# k1fm_wspr_tx-1_1.net
KiCad netlist of a schematic drawn in EAGLE
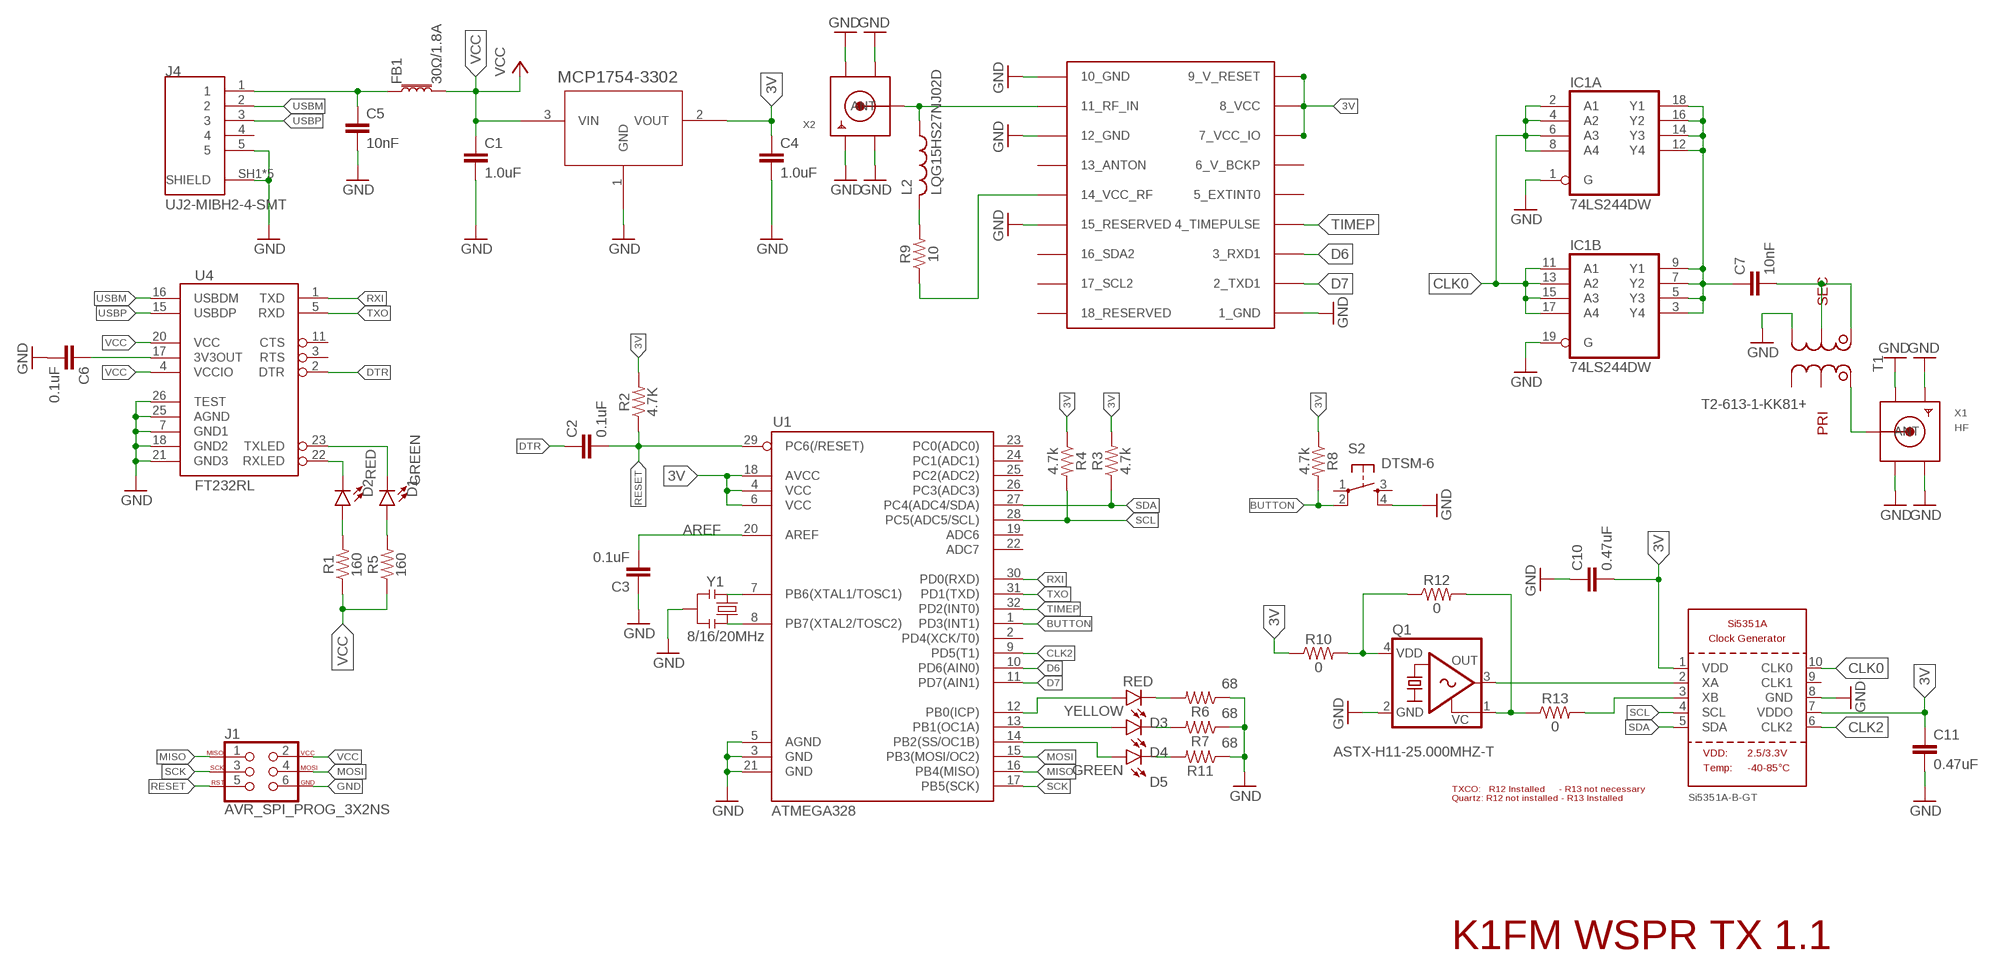
[diagram p0: schematic, sheet 1]

(export (version "E")
  (design (tool "Eeschema 10.0.6"))
  (components
    (comp (ref "C1")
      (value "1.0uF")
      (footprint "eagle-import:0603")
      (libsource (lib "eagle-import") (part "1.0UF-0603-16V-10%"))
    )
    (comp (ref "C2")
      (value "0.1uF")
      (footprint "eagle-import:0603")
      (libsource (lib "eagle-import") (part "0.1UF-0603-25V-5%"))
    )
    (comp (ref "C3")
      (value "0.1uF")
      (footprint "eagle-import:0603")
      (libsource (lib "eagle-import") (part "0.1UF-0603-25V-5%"))
    )
    (comp (ref "C4")
      (value "1.0uF")
      (footprint "eagle-import:0603")
      (libsource (lib "eagle-import") (part "1.0UF-0603-16V-10%"))
    )
    (comp (ref "C5")
      (value "10nF")
      (footprint "eagle-import:0603")
      (libsource (lib "eagle-import") (part "1.0UF-0603-16V-10%"))
    )
    (comp (ref "C6")
      (value "0.1uF")
      (footprint "eagle-import:0603")
      (libsource (lib "eagle-import") (part "0.1UF-0603-25V-5%"))
    )
    (comp (ref "C7")
      (value "10nF")
      (footprint "eagle-import:0603")
      (libsource (lib "eagle-import") (part "1.0UF-0603-16V-10%"))
    )
    (comp (ref "C10")
      (value "0.47uF")
      (footprint "eagle-import:0603")
      (libsource (lib "eagle-import") (part "0.1UF-0603-25V-5%"))
    )
    (comp (ref "C11")
      (value "0.47uF")
      (footprint "eagle-import:0603")
      (libsource (lib "eagle-import") (part "0.1UF-0603-25V-5%"))
    )
    (comp (ref "D1")
      (value "GREEN")
      (footprint "eagle-import:LED-0603")
      (libsource (lib "eagle-import") (part "LED0603"))
    )
    (comp (ref "D2")
      (value "RED")
      (footprint "eagle-import:LED-0603")
      (libsource (lib "eagle-import") (part "LED0603"))
    )
    (comp (ref "D3")
      (value "RED")
      (footprint "eagle-import:LED-0603")
      (libsource (lib "eagle-import") (part "LED0603"))
    )
    (comp (ref "D4")
      (value "YELLOW")
      (footprint "eagle-import:LED-0603")
      (libsource (lib "eagle-import") (part "LED0603"))
    )
    (comp (ref "D5")
      (value "GREEN")
      (footprint "eagle-import:LED-0603")
      (libsource (lib "eagle-import") (part "LED0603"))
    )
    (comp (ref "FB1")
      (value "30Ω/1.8A")
      (footprint "eagle-import:0603")
      (libsource (lib "eagle-import") (part "FERRITE_BEAD-0603"))
    )
    (comp (ref "GPS1")
      (value "UBLOX_MAX")
      (footprint "eagle-import:UBLOX_MAX")
      (libsource (lib "eagle-import") (part "UBLOX_MAX"))
    )
    (comp (ref "IC1")
      (value "74LS244DW")
      (footprint "eagle-import:SO20W")
      (libsource (lib "eagle-import") (part "74244DWLS"))
    )
    (comp (ref "J1")
      (value "AVR_SPI_PROG_3X2NS")
      (footprint "eagle-import:2X3-NS")
      (libsource (lib "eagle-import") (part "AVR_SPI_PROG_3X2NS"))
    )
    (comp (ref "J4")
      (value "UJ2-MIBH2-4-SMT")
      (footprint "eagle-import:CUI_UJ2-MIBH2-4-SMT")
      (fields (field (name "MANUFACTURER") "CUI INC"))
      (libsource (lib "eagle-import") (part "UJ2-MIBH2-4-SMT"))
    )
    (comp (ref "L2")
      (value "LQG15HS27NJ02D")
      (footprint "eagle-import:RESC0402_M")
      (libsource (lib "eagle-import") (part "INDUCTOR_0402_M"))
    )
    (comp (ref "Q1")
      (value "ASTX-H11-25.000MHZ-T")
      (footprint "eagle-import:3.2X2.5_KXO-84")
      (libsource (lib "eagle-import") (part "KXO-VCXO-SINE-84"))
    )
    (comp (ref "R1")
      (value "160")
      (footprint "eagle-import:0603")
      (libsource (lib "eagle-import") (part "4.7KOHM-0603-1/10W-1%"))
    )
    (comp (ref "R2")
      (value "4.7K")
      (footprint "eagle-import:0603")
      (libsource (lib "eagle-import") (part "10KOHM-0603-1/10W-1%"))
    )
    (comp (ref "R3")
      (value "4.7k")
      (footprint "eagle-import:0603")
      (libsource (lib "eagle-import") (part "4.7KOHM-0603-1/10W-1%"))
    )
    (comp (ref "R4")
      (value "4.7k")
      (footprint "eagle-import:0603")
      (libsource (lib "eagle-import") (part "4.7KOHM-0603-1/10W-1%"))
    )
    (comp (ref "R5")
      (value "160")
      (footprint "eagle-import:0603")
      (libsource (lib "eagle-import") (part "4.7KOHM-0603-1/10W-1%"))
    )
    (comp (ref "R6")
      (value "68")
      (footprint "eagle-import:0603")
      (libsource (lib "eagle-import") (part "4.7KOHM-0603-1/10W-1%"))
    )
    (comp (ref "R7")
      (value "68")
      (footprint "eagle-import:0603")
      (libsource (lib "eagle-import") (part "4.7KOHM-0603-1/10W-1%"))
    )
    (comp (ref "R8")
      (value "4.7k")
      (footprint "eagle-import:0603")
      (libsource (lib "eagle-import") (part "4.7KOHM-0603-1/10W-1%"))
    )
    (comp (ref "R9")
      (value "10")
      (footprint "eagle-import:0603")
      (libsource (lib "eagle-import") (part "10KOHM-0603-1/10W-1%"))
    )
    (comp (ref "R10")
      (value "0")
      (footprint "eagle-import:0603")
      (libsource (lib "eagle-import") (part "4.7KOHM-0603-1/10W-1%"))
    )
    (comp (ref "R11")
      (value "68")
      (footprint "eagle-import:0603")
      (libsource (lib "eagle-import") (part "4.7KOHM-0603-1/10W-1%"))
    )
    (comp (ref "R12")
      (value "0")
      (footprint "eagle-import:0603")
      (libsource (lib "eagle-import") (part "4.7KOHM-0603-1/10W-1%"))
    )
    (comp (ref "R13")
      (value "0")
      (footprint "eagle-import:0603")
      (libsource (lib "eagle-import") (part "4.7KOHM-0603-1/10W-1%"))
    )
    (comp (ref "S2")
      (value "DTSM-6")
      (footprint "eagle-import:DTSM-6")
      (libsource (lib "eagle-import") (part "DTSM-6"))
    )
    (comp (ref "T1")
      (value "T2-613-1-KK81+")
      (footprint "eagle-import:KK81")
      (libsource (lib "eagle-import") (part "TT1-6"))
    )
    (comp (ref "U1")
      (value "ATMEGA328")
      (footprint "eagle-import:TQFP32-08")
      (libsource (lib "eagle-import") (part "ATMEGA168"))
    )
    (comp (ref "U2")
      (value "Si5351A-B-GT")
      (footprint "eagle-import:MSOP10")
      (libsource (lib "eagle-import") (part "SI5351A"))
    )
    (comp (ref "U3")
      (value "MCP1754X-XXXXX/C")
      (footprint "eagle-import:SOT-23A_MC")
      (libsource (lib "eagle-import") (part "MCP1754X-XXXXX/C"))
    )
    (comp (ref "U4")
      (value "FT232RL")
      (footprint "eagle-import:SSOP28DB")
      (libsource (lib "eagle-import") (part "FT232RL-BASICSSOP"))
    )
    (comp (ref "X1")
      (value "HF")
      (footprint "eagle-import:SMA_EDGELAUNCH")
      (libsource (lib "eagle-import") (part "SMACONNECTOR_EDGE"))
    )
    (comp (ref "X2")
      (value "SMACONNECTOR_EDGE")
      (footprint "eagle-import:SMA_EDGELAUNCH")
      (libsource (lib "eagle-import") (part "SMACONNECTOR_EDGE"))
    )
    (comp (ref "Y1")
      (value "8/16/20MHz")
      (footprint "eagle-import:RESONATOR-SMD-1_1")
      (libsource (lib "eagle-import") (part "RESONATOR1{colon}1"))
    )
  )
  (nets
    (net (code "1") (name "/AREF") (class "Default")
      (node (ref "C3") (pin "2") (pinfunction "2_2") (pintype "passive"))
      (node (ref "U1") (pin "20") (pinfunction "AREF_20") (pintype "bidirectional"))
    )
    (net (code "2") (name "3V") (class "Default")
      (node (ref "C10") (pin "2") (pinfunction "2_2") (pintype "passive"))
      (node (ref "C11") (pin "1") (pinfunction "1_1") (pintype "passive"))
      (node (ref "C4") (pin "1") (pinfunction "1_1") (pintype "passive"))
      (node (ref "GPS1") (pin "7_VCC_IO") (pinfunction "7_VCC_IO_7_VCC_IO") (pintype "power_in"))
      (node (ref "GPS1") (pin "8_VCC") (pinfunction "8_VCC_8_VCC") (pintype "power_in"))
      (node (ref "GPS1") (pin "9_V_RESET") (pinfunction "9_V_RESET_9_V_RESET") (pintype "power_in"))
      (node (ref "R10") (pin "1") (pinfunction "1_1") (pintype "passive"))
      (node (ref "R2") (pin "2") (pinfunction "2_2") (pintype "passive"))
      (node (ref "R3") (pin "2") (pinfunction "2_2") (pintype "passive"))
      (node (ref "R4") (pin "1") (pinfunction "1_1") (pintype "passive"))
      (node (ref "R8") (pin "1") (pinfunction "1_1") (pintype "passive"))
      (node (ref "U1") (pin "18") (pinfunction "AVCC_18") (pintype "bidirectional"))
      (node (ref "U1") (pin "4") (pinfunction "VCC_4") (pintype "bidirectional"))
      (node (ref "U1") (pin "6") (pinfunction "VCC_6") (pintype "bidirectional"))
      (node (ref "U2") (pin "1") (pinfunction "VDD_1") (pintype "power_in"))
      (node (ref "U2") (pin "7") (pinfunction "VDDO_7") (pintype "power_in"))
      (node (ref "U3") (pin "2") (pinfunction "VOUT_2") (pintype "passive"))
    )
    (net (code "3") (name "BUTTON") (class "Default")
      (node (ref "R8") (pin "2") (pinfunction "2_2") (pintype "passive"))
      (node (ref "S2") (pin "2") (pinfunction "2_2") (pintype "passive"))
      (node (ref "U1") (pin "1") (pinfunction "PD3(INT1)_1") (pintype "bidirectional"))
    )
    (net (code "4") (name "CLK0") (class "Default")
      (node (ref "IC1") (pin "11") (pinfunction "A1_11") (pintype "input"))
      (node (ref "IC1") (pin "13") (pinfunction "A2_13") (pintype "input"))
      (node (ref "IC1") (pin "15") (pinfunction "A3_15") (pintype "input"))
      (node (ref "IC1") (pin "17") (pinfunction "A4_17") (pintype "input"))
      (node (ref "IC1") (pin "2") (pinfunction "A1_2") (pintype "input"))
      (node (ref "IC1") (pin "4") (pinfunction "A2_4") (pintype "input"))
      (node (ref "IC1") (pin "6") (pinfunction "A3_6") (pintype "input"))
      (node (ref "IC1") (pin "8") (pinfunction "A4_8") (pintype "input"))
      (node (ref "U2") (pin "10") (pinfunction "CLK0_10") (pintype "output"))
    )
    (net (code "5") (name "CLK2") (class "Default")
      (node (ref "U1") (pin "9") (pinfunction "PD5(T1)_9") (pintype "bidirectional"))
      (node (ref "U2") (pin "6") (pinfunction "CLK2_6") (pintype "output"))
    )
    (net (code "6") (name "D6") (class "Default")
      (node (ref "GPS1") (pin "3_RXD1") (pinfunction "3_RXD1_3_RXD1") (pintype "bidirectional"))
      (node (ref "U1") (pin "10") (pinfunction "PD6(AIN0)_10") (pintype "bidirectional"))
    )
    (net (code "7") (name "D7") (class "Default")
      (node (ref "GPS1") (pin "2_TXD1") (pinfunction "2_TXD1_2_TXD1") (pintype "bidirectional"))
      (node (ref "U1") (pin "11") (pinfunction "PD7(AIN1)_11") (pintype "bidirectional"))
    )
    (net (code "8") (name "DTR") (class "Default")
      (node (ref "C2") (pin "1") (pinfunction "1_1") (pintype "passive"))
      (node (ref "U4") (pin "2") (pinfunction "DTR_2") (pintype "bidirectional"))
    )
    (net (code "9") (name "GND") (class "Default")
      (node (ref "C1") (pin "2") (pinfunction "2_2") (pintype "passive"))
      (node (ref "C10") (pin "1") (pinfunction "1_1") (pintype "passive"))
      (node (ref "C11") (pin "2") (pinfunction "2_2") (pintype "passive"))
      (node (ref "C3") (pin "1") (pinfunction "1_1") (pintype "passive"))
      (node (ref "C4") (pin "2") (pinfunction "2_2") (pintype "passive"))
      (node (ref "C5") (pin "2") (pinfunction "2_2") (pintype "passive"))
      (node (ref "C6") (pin "2") (pinfunction "2_2") (pintype "passive"))
      (node (ref "GPS1") (pin "10_GND") (pinfunction "10_GND_10_GND") (pintype "power_in"))
      (node (ref "GPS1") (pin "12_GND") (pinfunction "12_GND_12_GND") (pintype "power_in"))
      (node (ref "GPS1") (pin "15_RESERVED") (pinfunction "15_RESERVED_15_RESERVED") (pintype "bidirectional"))
      (node (ref "GPS1") (pin "1_GND") (pinfunction "1_GND_1_GND") (pintype "power_in"))
      (node (ref "IC1") (pin "1") (pinfunction "G_1") (pintype "input"))
      (node (ref "IC1") (pin "19") (pinfunction "G_19") (pintype "input"))
      (node (ref "J1") (pin "6") (pinfunction "6_6") (pintype "passive"))
      (node (ref "J4") (pin "5") (pinfunction "5_5") (pintype "passive"))
      (node (ref "J4") (pin "SH1") (pinfunction "SHIELD_SH1") (pintype "passive"))
      (node (ref "J4") (pin "SH2") (pinfunction "SHIELD_SH2") (pintype "passive"))
      (node (ref "J4") (pin "SH3") (pinfunction "SHIELD_SH3") (pintype "passive"))
      (node (ref "J4") (pin "SH4") (pinfunction "SHIELD_SH4") (pintype "passive"))
      (node (ref "J4") (pin "SH5") (pinfunction "SHIELD_SH5") (pintype "passive"))
      (node (ref "Q1") (pin "2") (pinfunction "GND_2") (pintype "power_in"))
      (node (ref "R11") (pin "1") (pinfunction "1_1") (pintype "passive"))
      (node (ref "R6") (pin "1") (pinfunction "1_1") (pintype "passive"))
      (node (ref "R7") (pin "1") (pinfunction "1_1") (pintype "passive"))
      (node (ref "S2") (pin "4") (pinfunction "4_4") (pintype "passive"))
      (node (ref "T1") (pin "1") (pinfunction "S2_1") (pintype "passive"))
      (node (ref "U1") (pin "21") (pinfunction "GND_21") (pintype "bidirectional"))
      (node (ref "U1") (pin "3") (pinfunction "GND_3") (pintype "bidirectional"))
      (node (ref "U1") (pin "5") (pinfunction "AGND_5") (pintype "bidirectional"))
      (node (ref "U2") (pin "8") (pinfunction "GND_8") (pintype "power_in"))
      (node (ref "U3") (pin "1") (pinfunction "GND_1") (pintype "passive"))
      (node (ref "U4") (pin "18") (pinfunction "GND2_18") (pintype "power_in"))
      (node (ref "U4") (pin "21") (pinfunction "GND3_21") (pintype "power_in"))
      (node (ref "U4") (pin "25") (pinfunction "AGND_25") (pintype "power_in"))
      (node (ref "U4") (pin "26") (pinfunction "TEST_26") (pintype "input"))
      (node (ref "U4") (pin "7") (pinfunction "GND1_7") (pintype "power_in"))
      (node (ref "X1") (pin "GND@1") (pinfunction "GND4_GND@1") (pintype "power_in"))
      (node (ref "X1") (pin "GND@2") (pinfunction "GND3_GND@2") (pintype "power_in"))
      (node (ref "X1") (pin "GND@3") (pinfunction "GND2_GND@3") (pintype "power_in"))
      (node (ref "X1") (pin "GND@4") (pinfunction "GND1_GND@4") (pintype "power_in"))
      (node (ref "X2") (pin "GND@1") (pinfunction "GND4_GND@1") (pintype "power_in"))
      (node (ref "X2") (pin "GND@2") (pinfunction "GND3_GND@2") (pintype "power_in"))
      (node (ref "X2") (pin "GND@3") (pinfunction "GND2_GND@3") (pintype "power_in"))
      (node (ref "X2") (pin "GND@4") (pinfunction "GND1_GND@4") (pintype "power_in"))
      (node (ref "Y1") (pin "2") (pinfunction "2_2") (pintype "passive"))
    )
    (net (code "10") (name "MISO") (class "Default")
      (node (ref "J1") (pin "1") (pinfunction "1_1") (pintype "passive"))
      (node (ref "U1") (pin "16") (pinfunction "PB4(MISO)_16") (pintype "bidirectional"))
    )
    (net (code "11") (name "MOSI") (class "Default")
      (node (ref "J1") (pin "4") (pinfunction "4_4") (pintype "passive"))
      (node (ref "U1") (pin "15") (pinfunction "PB3(MOSI/OC2)_15") (pintype "bidirectional"))
    )
    (net (code "12") (name "Net-(C5-Pad1)") (class "Default")
      (node (ref "C5") (pin "1") (pinfunction "1_1") (pintype "passive"))
      (node (ref "FB1") (pin "1") (pinfunction "1_1") (pintype "passive"))
      (node (ref "J4") (pin "1") (pinfunction "1_1") (pintype "passive"))
    )
    (net (code "13") (name "Net-(D1-PadA)") (class "Default")
      (node (ref "D1") (pin "A") (pinfunction "A_A") (pintype "passive"))
      (node (ref "R5") (pin "2") (pinfunction "2_2") (pintype "passive"))
    )
    (net (code "14") (name "Net-(D2-PadA)") (class "Default")
      (node (ref "D2") (pin "A") (pinfunction "A_A") (pintype "passive"))
      (node (ref "R1") (pin "2") (pinfunction "2_2") (pintype "passive"))
    )
    (net (code "15") (name "Net-(D3-PadC)") (class "Default")
      (node (ref "D3") (pin "C") (pinfunction "C_C") (pintype "passive"))
      (node (ref "R6") (pin "2") (pinfunction "2_2") (pintype "passive"))
    )
    (net (code "16") (name "Net-(D4-PadC)") (class "Default")
      (node (ref "D4") (pin "C") (pinfunction "C_C") (pintype "passive"))
      (node (ref "R7") (pin "2") (pinfunction "2_2") (pintype "passive"))
    )
    (net (code "17") (name "Net-(D5-PadC)") (class "Default")
      (node (ref "D5") (pin "C") (pinfunction "C_C") (pintype "passive"))
      (node (ref "R11") (pin "2") (pinfunction "2_2") (pintype "passive"))
    )
    (net (code "18") (name "Net-(GPS1-Pad14_VCC_RF)") (class "Default")
      (node (ref "GPS1") (pin "14_VCC_RF") (pinfunction "14_VCC_RF_14_VCC_RF") (pintype "bidirectional"))
      (node (ref "R9") (pin "1") (pinfunction "1_1") (pintype "passive"))
    )
    (net (code "19") (name "Net-(IC1A-Y1)") (class "Default")
      (node (ref "C7") (pin "1") (pinfunction "1_1") (pintype "passive"))
      (node (ref "IC1") (pin "12") (pinfunction "Y4_12") (pintype "tri_state"))
      (node (ref "IC1") (pin "14") (pinfunction "Y3_14") (pintype "tri_state"))
      (node (ref "IC1") (pin "16") (pinfunction "Y2_16") (pintype "tri_state"))
      (node (ref "IC1") (pin "18") (pinfunction "Y1_18") (pintype "tri_state"))
      (node (ref "IC1") (pin "3") (pinfunction "Y4_3") (pintype "tri_state"))
      (node (ref "IC1") (pin "5") (pinfunction "Y3_5") (pintype "tri_state"))
      (node (ref "IC1") (pin "7") (pinfunction "Y2_7") (pintype "tri_state"))
      (node (ref "IC1") (pin "9") (pinfunction "Y1_9") (pintype "tri_state"))
    )
    (net (code "20") (name "Net-(L2-Pad2)") (class "Default")
      (node (ref "L2") (pin "2") (pinfunction "2_2") (pintype "passive"))
      (node (ref "R9") (pin "2") (pinfunction "2_2") (pintype "passive"))
    )
    (net (code "21") (name "Net-(Q1-OUT)") (class "Default")
      (node (ref "Q1") (pin "3") (pinfunction "OUT_3") (pintype "output"))
      (node (ref "U2") (pin "2") (pinfunction "XA_2") (pintype "input"))
    )
    (net (code "22") (name "Net-(Q1-VC)") (class "Default")
      (node (ref "Q1") (pin "1") (pinfunction "VC_1") (pintype "input"))
      (node (ref "R12") (pin "2") (pinfunction "2_2") (pintype "passive"))
      (node (ref "R13") (pin "1") (pinfunction "1_1") (pintype "passive"))
    )
    (net (code "23") (name "Net-(Q1-VDD)") (class "Default")
      (node (ref "Q1") (pin "4") (pinfunction "VDD_4") (pintype "power_in"))
      (node (ref "R10") (pin "2") (pinfunction "2_2") (pintype "passive"))
      (node (ref "R12") (pin "1") (pinfunction "1_1") (pintype "passive"))
    )
    (net (code "24") (name "Net-(T1-P1)") (class "Default")
      (node (ref "T1") (pin "4") (pinfunction "P1_4") (pintype "passive"))
      (node (ref "X1") (pin "P") (pinfunction "ANT_P") (pintype "bidirectional"))
    )
    (net (code "25") (name "Net-(T1-S1)") (class "Default")
      (node (ref "C7") (pin "2") (pinfunction "2_2") (pintype "passive"))
      (node (ref "T1") (pin "2") (pinfunction "ST_2") (pintype "passive"))
      (node (ref "T1") (pin "3") (pinfunction "S1_3") (pintype "passive"))
    )
    (net (code "26") (name "Net-(U1-PB0(ICP))") (class "Default")
      (node (ref "D3") (pin "A") (pinfunction "A_A") (pintype "passive"))
      (node (ref "U1") (pin "12") (pinfunction "PB0(ICP)_12") (pintype "bidirectional"))
    )
    (net (code "27") (name "Net-(U1-PB1(OC1A))") (class "Default")
      (node (ref "D4") (pin "A") (pinfunction "A_A") (pintype "passive"))
      (node (ref "U1") (pin "13") (pinfunction "PB1(OC1A)_13") (pintype "bidirectional"))
    )
    (net (code "28") (name "Net-(U1-PB2(SS{slash}OC1B))") (class "Default")
      (node (ref "D5") (pin "A") (pinfunction "A_A") (pintype "passive"))
      (node (ref "U1") (pin "14") (pinfunction "PB2(SS/OC1B)_14") (pintype "bidirectional"))
    )
    (net (code "29") (name "Net-(U1-PB6(XTAL1{slash}TOSC1))") (class "Default")
      (node (ref "U1") (pin "7") (pinfunction "PB6(XTAL1/TOSC1)_7") (pintype "bidirectional"))
      (node (ref "Y1") (pin "1") (pinfunction "1_1") (pintype "passive"))
    )
    (net (code "30") (name "Net-(U1-PB7(XTAL2{slash}TOSC2))") (class "Default")
      (node (ref "U1") (pin "8") (pinfunction "PB7(XTAL2/TOSC2)_8") (pintype "bidirectional"))
      (node (ref "Y1") (pin "3") (pinfunction "3_3") (pintype "passive"))
    )
    (net (code "31") (name "Net-(U2-XB)") (class "Default")
      (node (ref "R13") (pin "2") (pinfunction "2_2") (pintype "passive"))
      (node (ref "U2") (pin "3") (pinfunction "XB_3") (pintype "input"))
    )
    (net (code "32") (name "Net-(U4-3V3OUT)") (class "Default")
      (node (ref "C6") (pin "1") (pinfunction "1_1") (pintype "passive"))
      (node (ref "U4") (pin "17") (pinfunction "3V3OUT_17") (pintype "output"))
    )
    (net (code "33") (name "Net-(U4-RXLED)") (class "Default")
      (node (ref "D2") (pin "C") (pinfunction "C_C") (pintype "passive"))
      (node (ref "U4") (pin "22") (pinfunction "RXLED_22") (pintype "bidirectional"))
    )
    (net (code "34") (name "Net-(U4-TXLED)") (class "Default")
      (node (ref "D1") (pin "C") (pinfunction "C_C") (pintype "passive"))
      (node (ref "U4") (pin "23") (pinfunction "TXLED_23") (pintype "bidirectional"))
    )
    (net (code "35") (name "Net-(X2-ANT)") (class "Default")
      (node (ref "GPS1") (pin "11_RF_IN") (pinfunction "11_RF_IN_11_RF_IN") (pintype "bidirectional"))
      (node (ref "L2") (pin "1") (pinfunction "1_1") (pintype "passive"))
      (node (ref "X2") (pin "P") (pinfunction "ANT_P") (pintype "bidirectional"))
    )
    (net (code "36") (name "RESET") (class "Default")
      (node (ref "C2") (pin "2") (pinfunction "2_2") (pintype "passive"))
      (node (ref "J1") (pin "5") (pinfunction "5_5") (pintype "passive"))
      (node (ref "R2") (pin "1") (pinfunction "1_1") (pintype "passive"))
      (node (ref "U1") (pin "29") (pinfunction "PC6(/RESET)_29") (pintype "bidirectional"))
    )
    (net (code "37") (name "RXI") (class "Default")
      (node (ref "U1") (pin "30") (pinfunction "PD0(RXD)_30") (pintype "bidirectional"))
      (node (ref "U4") (pin "1") (pinfunction "TXD_1") (pintype "output"))
    )
    (net (code "38") (name "SCK") (class "Default")
      (node (ref "J1") (pin "3") (pinfunction "3_3") (pintype "passive"))
      (node (ref "U1") (pin "17") (pinfunction "PB5(SCK)_17") (pintype "bidirectional"))
    )
    (net (code "39") (name "SCL") (class "Default")
      (node (ref "R4") (pin "2") (pinfunction "2_2") (pintype "passive"))
      (node (ref "U1") (pin "28") (pinfunction "PC5(ADC5/SCL)_28") (pintype "bidirectional"))
      (node (ref "U2") (pin "4") (pinfunction "SCL_4") (pintype "input"))
    )
    (net (code "40") (name "SDA") (class "Default")
      (node (ref "R3") (pin "1") (pinfunction "1_1") (pintype "passive"))
      (node (ref "U1") (pin "27") (pinfunction "PC4(ADC4/SDA)_27") (pintype "bidirectional"))
      (node (ref "U2") (pin "5") (pinfunction "SDA_5") (pintype "bidirectional"))
    )
    (net (code "41") (name "TIMEP") (class "Default")
      (node (ref "GPS1") (pin "4_TIMEPULSE") (pinfunction "4_TIMEPULSE_4_TIMEPULSE") (pintype "bidirectional"))
      (node (ref "U1") (pin "32") (pinfunction "PD2(INT0)_32") (pintype "bidirectional"))
    )
    (net (code "42") (name "TXO") (class "Default")
      (node (ref "U1") (pin "31") (pinfunction "PD1(TXD)_31") (pintype "bidirectional"))
      (node (ref "U4") (pin "5") (pinfunction "RXD_5") (pintype "input"))
    )
    (net (code "43") (name "USBM") (class "Default")
      (node (ref "J4") (pin "2") (pinfunction "2_2") (pintype "passive"))
      (node (ref "U4") (pin "16") (pinfunction "USBDM_16") (pintype "bidirectional"))
    )
    (net (code "44") (name "USBP") (class "Default")
      (node (ref "J4") (pin "3") (pinfunction "3_3") (pintype "passive"))
      (node (ref "U4") (pin "15") (pinfunction "USBDP_15") (pintype "bidirectional"))
    )
    (net (code "45") (name "VCC") (class "Default")
      (node (ref "C1") (pin "1") (pinfunction "1_1") (pintype "passive"))
      (node (ref "FB1") (pin "2") (pinfunction "2_2") (pintype "passive"))
      (node (ref "J1") (pin "2") (pinfunction "2_2") (pintype "passive"))
      (node (ref "R1") (pin "1") (pinfunction "1_1") (pintype "passive"))
      (node (ref "R5") (pin "1") (pinfunction "1_1") (pintype "passive"))
      (node (ref "U3") (pin "3") (pinfunction "VIN_3") (pintype "passive"))
      (node (ref "U4") (pin "20") (pinfunction "VCC_20") (pintype "power_in"))
      (node (ref "U4") (pin "4") (pinfunction "VCCIO_4") (pintype "power_in"))
    )
    (net (code "46") (name "unconnected-(GPS1-Pad5_EXTINT0)") (class "Default")
      (node (ref "GPS1") (pin "5_EXTINT0") (pinfunction "5_EXTINT0_5_EXTINT0") (pintype "bidirectional"))
    )
    (net (code "47") (name "unconnected-(GPS1-Pad6_V_BCKP)") (class "Default")
      (node (ref "GPS1") (pin "6_V_BCKP") (pinfunction "6_V_BCKP_6_V_BCKP") (pintype "bidirectional"))
    )
    (net (code "48") (name "unconnected-(GPS1-Pad13_ANTON)") (class "Default")
      (node (ref "GPS1") (pin "13_ANTON") (pinfunction "13_ANTON_13_ANTON") (pintype "bidirectional"))
    )
    (net (code "49") (name "unconnected-(GPS1-Pad16_SDA2)") (class "Default")
      (node (ref "GPS1") (pin "16_SDA2") (pinfunction "16_SDA2_16_SDA2") (pintype "bidirectional"))
    )
    (net (code "50") (name "unconnected-(GPS1-Pad17_SCL2)") (class "Default")
      (node (ref "GPS1") (pin "17_SCL2") (pinfunction "17_SCL2_17_SCL2") (pintype "bidirectional"))
    )
    (net (code "51") (name "unconnected-(GPS1-Pad18_RESERVED)") (class "Default")
      (node (ref "GPS1") (pin "18_RESERVED") (pinfunction "18_RESERVED_18_RESERVED") (pintype "bidirectional"))
    )
    (net (code "52") (name "unconnected-(J4-Pad4)") (class "Default")
      (node (ref "J4") (pin "4") (pinfunction "4_4") (pintype "passive"))
    )
    (net (code "53") (name "unconnected-(S2-Pad1)") (class "Default")
      (node (ref "S2") (pin "1") (pinfunction "1_1") (pintype "passive"))
    )
    (net (code "54") (name "unconnected-(S2-Pad3)") (class "Default")
      (node (ref "S2") (pin "3") (pinfunction "3_3") (pintype "passive"))
    )
    (net (code "55") (name "unconnected-(T1-P2-Pad6)") (class "Default")
      (node (ref "T1") (pin "6") (pinfunction "P2_6") (pintype "passive"))
    )
    (net (code "56") (name "unconnected-(T1-PT-Pad5)") (class "Default")
      (node (ref "T1") (pin "5") (pinfunction "PT_5") (pintype "passive"))
    )
    (net (code "57") (name "unconnected-(U1-ADC6-Pad19)") (class "Default")
      (node (ref "U1") (pin "19") (pinfunction "ADC6_19") (pintype "bidirectional"))
    )
    (net (code "58") (name "unconnected-(U1-ADC7-Pad22)") (class "Default")
      (node (ref "U1") (pin "22") (pinfunction "ADC7_22") (pintype "bidirectional"))
    )
    (net (code "59") (name "unconnected-(U1-PC0(ADC0)-Pad23)") (class "Default")
      (node (ref "U1") (pin "23") (pinfunction "PC0(ADC0)_23") (pintype "bidirectional"))
    )
    (net (code "60") (name "unconnected-(U1-PC1(ADC1)-Pad24)") (class "Default")
      (node (ref "U1") (pin "24") (pinfunction "PC1(ADC1)_24") (pintype "bidirectional"))
    )
    (net (code "61") (name "unconnected-(U1-PC2(ADC2)-Pad25)") (class "Default")
      (node (ref "U1") (pin "25") (pinfunction "PC2(ADC2)_25") (pintype "bidirectional"))
    )
    (net (code "62") (name "unconnected-(U1-PC3(ADC3)-Pad26)") (class "Default")
      (node (ref "U1") (pin "26") (pinfunction "PC3(ADC3)_26") (pintype "bidirectional"))
    )
    (net (code "63") (name "unconnected-(U1-PD4(XCK{slash}T0)-Pad2)") (class "Default")
      (node (ref "U1") (pin "2") (pinfunction "PD4(XCK/T0)_2") (pintype "bidirectional"))
    )
    (net (code "64") (name "unconnected-(U2-CLK1-Pad9)") (class "Default")
      (node (ref "U2") (pin "9") (pinfunction "CLK1_9") (pintype "output"))
    )
    (net (code "65") (name "unconnected-(U4-CTS-Pad11)") (class "Default")
      (node (ref "U4") (pin "11") (pinfunction "CTS_11") (pintype "bidirectional"))
    )
    (net (code "66") (name "unconnected-(U4-RTS-Pad3)") (class "Default")
      (node (ref "U4") (pin "3") (pinfunction "RTS_3") (pintype "bidirectional"))
    )
  )
)
